# 3phasecntrl-rev2-1.net
KiCad netlist of a schematic drawn in EAGLE
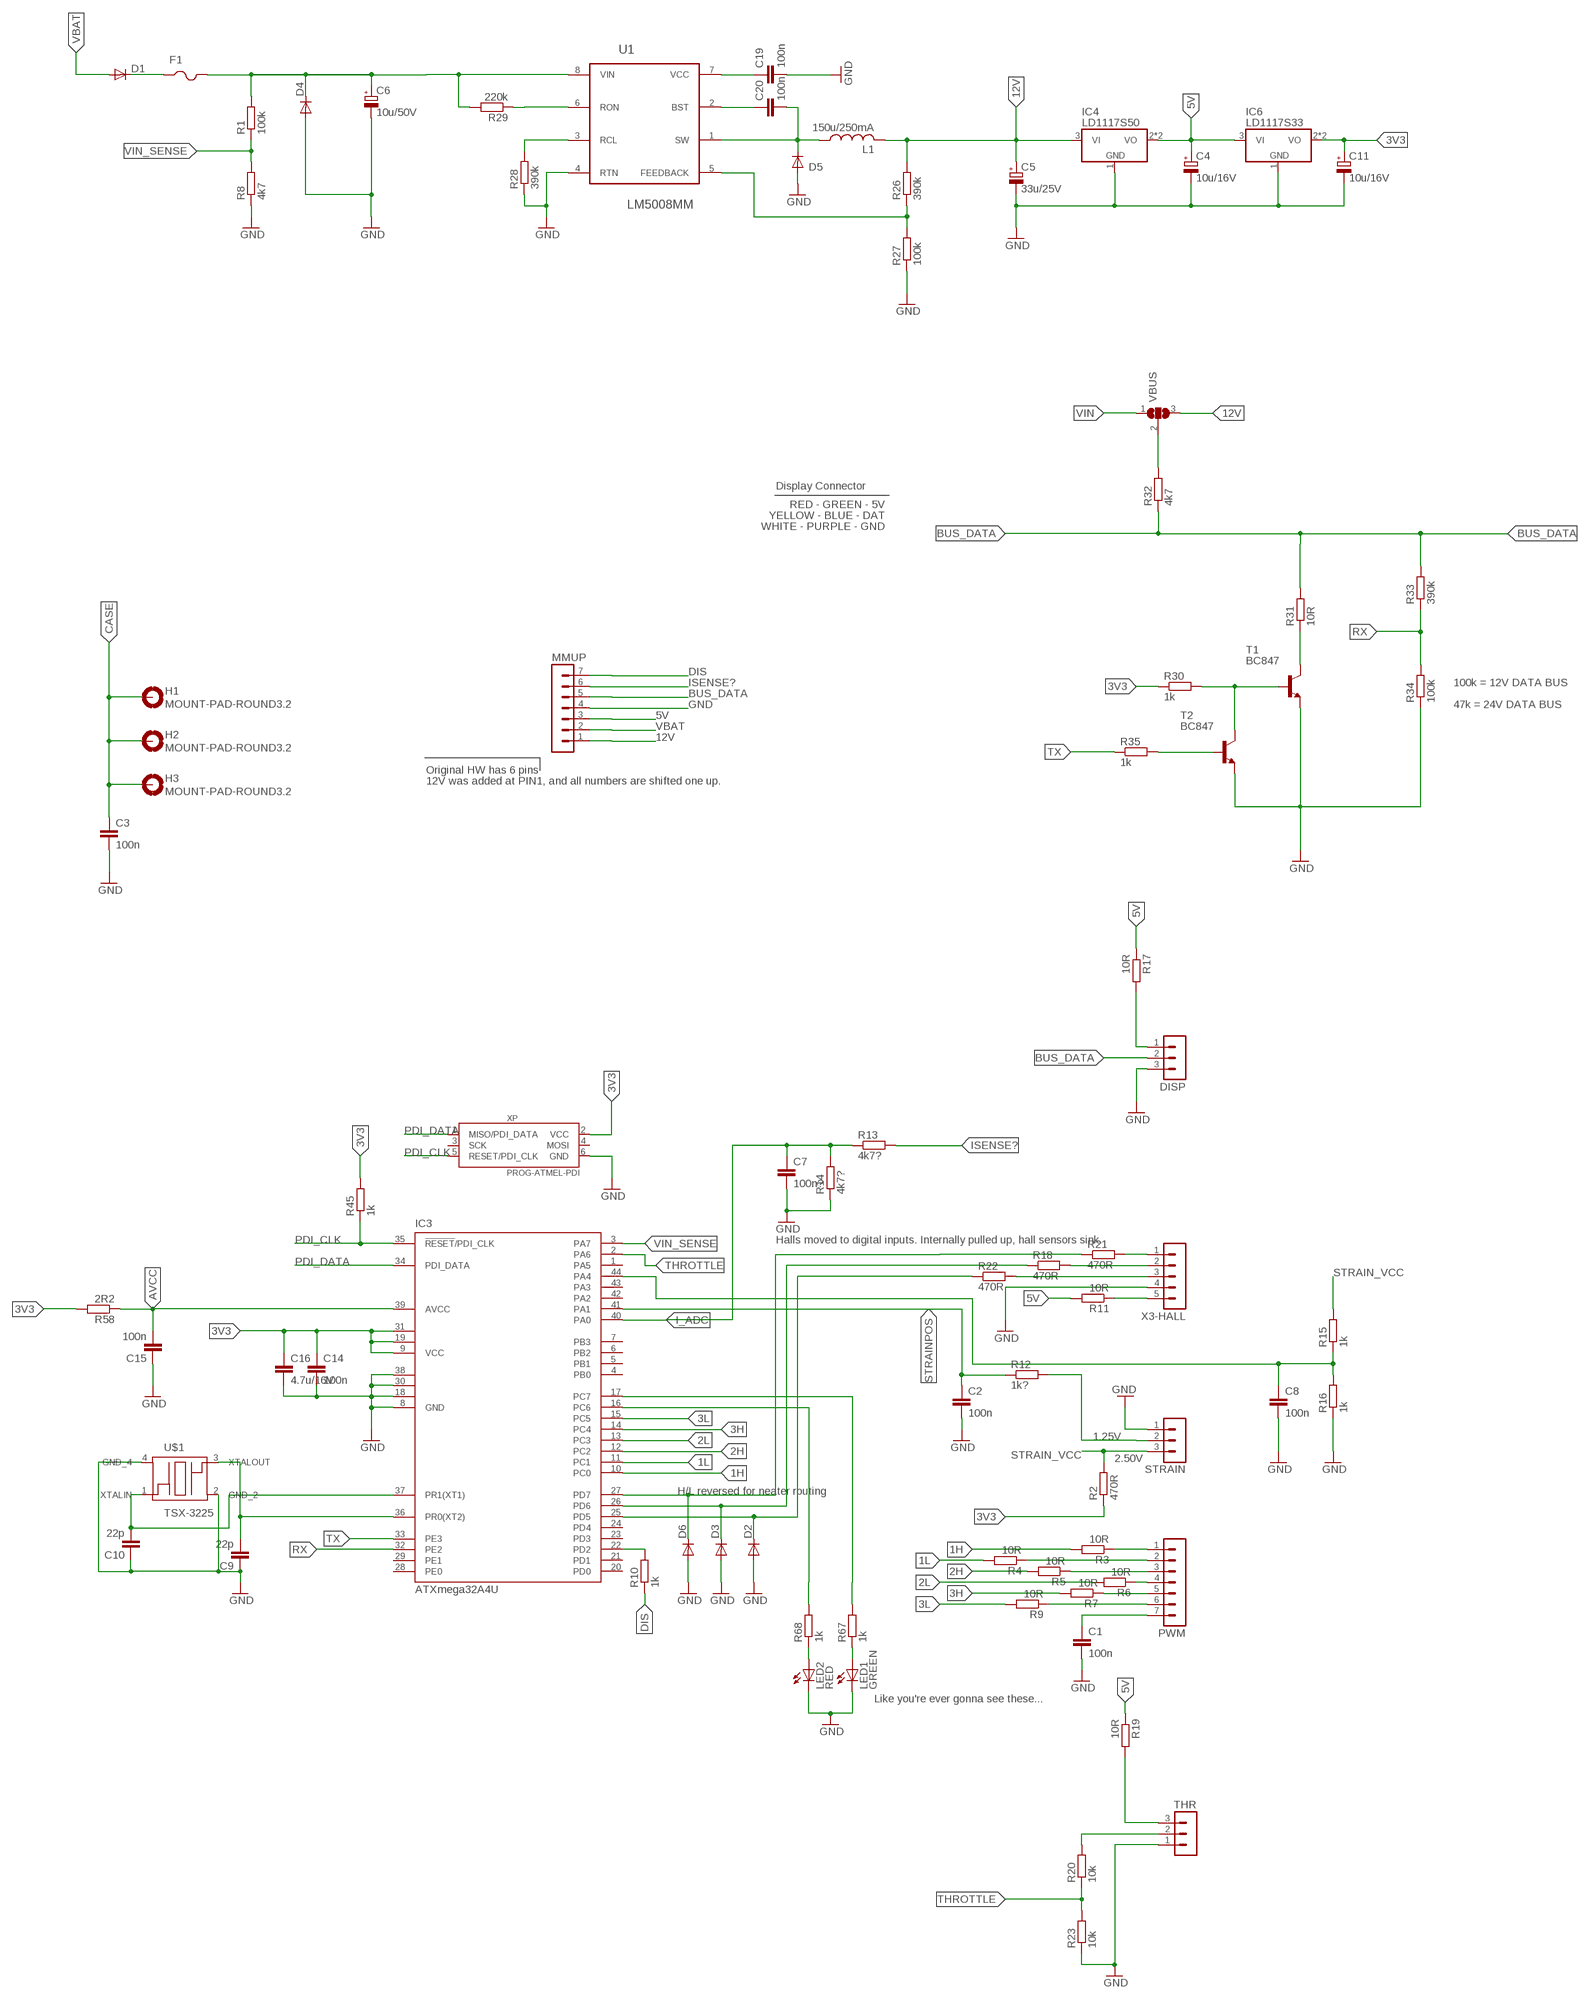
[diagram p0: schematic, sheet 1]

(export (version "E")
  (design (tool "Eeschema 10.0.6"))
  (components
    (comp (ref "C1")
      (value "100n")
      (footprint "eagle-import:C0805K")
      (libsource (lib "eagle-import") (part "C-EUC0805K"))
    )
    (comp (ref "C2")
      (value "100n")
      (footprint "eagle-import:C0805K")
      (libsource (lib "eagle-import") (part "C-EUC0805K"))
    )
    (comp (ref "C3")
      (value "100n")
      (footprint "eagle-import:C0805K")
      (libsource (lib "eagle-import") (part "C-EUC0805K"))
    )
    (comp (ref "C4")
      (value "10u/16V")
      (footprint "eagle-import:153CLV-0405")
      (libsource (lib "eagle-import") (part "CPOL-EU153CLV-0405"))
    )
    (comp (ref "C5")
      (value "33u/25V")
      (footprint "eagle-import:153CLV-0605")
      (libsource (lib "eagle-import") (part "CPOL-EU153CLV-0605"))
    )
    (comp (ref "C6")
      (value "10u/50V")
      (footprint "eagle-import:153CLV-0605")
      (libsource (lib "eagle-import") (part "CPOL-EU153CLV-0605"))
    )
    (comp (ref "C7")
      (value "100n?")
      (footprint "eagle-import:C0805K")
      (libsource (lib "eagle-import") (part "C-EUC0805K"))
    )
    (comp (ref "C8")
      (value "100n")
      (footprint "eagle-import:C0805K")
      (libsource (lib "eagle-import") (part "C-EUC0805K"))
    )
    (comp (ref "C9")
      (value "22p")
      (footprint "eagle-import:C0805K")
      (libsource (lib "eagle-import") (part "C-EUC0805K"))
    )
    (comp (ref "C10")
      (value "22p")
      (footprint "eagle-import:C0805K")
      (libsource (lib "eagle-import") (part "C-EUC0805K"))
    )
    (comp (ref "C11")
      (value "10u/16V")
      (footprint "eagle-import:153CLV-0405")
      (libsource (lib "eagle-import") (part "CPOL-EU153CLV-0405"))
    )
    (comp (ref "C14")
      (value "100n")
      (footprint "eagle-import:C0805K")
      (libsource (lib "eagle-import") (part "C-EUC0805K"))
    )
    (comp (ref "C15")
      (value "100n")
      (footprint "eagle-import:C0805K")
      (libsource (lib "eagle-import") (part "C-EUC0805K"))
    )
    (comp (ref "C16")
      (value "4.7u/16V")
      (footprint "eagle-import:C0805K")
      (libsource (lib "eagle-import") (part "C-EUC0805K"))
    )
    (comp (ref "C19")
      (value "100n")
      (footprint "eagle-import:C0805K")
      (libsource (lib "eagle-import") (part "C-EUC0805K"))
    )
    (comp (ref "C20")
      (value "100n")
      (footprint "eagle-import:C0805K")
      (libsource (lib "eagle-import") (part "C-EUC0805K"))
    )
    (comp (ref "D1")
      (value "BAT46WH")
      (footprint "eagle-import:SMB")
      (libsource (lib "eagle-import") (part "DIODE-SMB"))
    )
    (comp (ref "D2")
      (value "PTVS3V3S1UTR")
      (footprint "eagle-import:SOD123")
      (libsource (lib "eagle-import") (part "DIODE-SOD123"))
    )
    (comp (ref "D3")
      (value "PTVS3V3S1UTR")
      (footprint "eagle-import:SOD123")
      (libsource (lib "eagle-import") (part "DIODE-SOD123"))
    )
    (comp (ref "D4")
      (value "SM6T39A")
      (footprint "eagle-import:SMB")
      (libsource (lib "eagle-import") (part "DIODE-SMB"))
    )
    (comp (ref "D5")
      (value "BAT46WH")
      (footprint "eagle-import:SOD323-W")
      (libsource (lib "eagle-import") (part "DIODE-SOD323-W"))
    )
    (comp (ref "D6")
      (value "PTVS3V3S1UTR")
      (footprint "eagle-import:SOD123")
      (libsource (lib "eagle-import") (part "DIODE-SOD123"))
    )
    (comp (ref "DISP")
      (value "MA03-1")
      (footprint "eagle-import:MA03-1")
      (fields (field (name "OC_FARNELL") "unknown") (field (name "OC_NEWARK") "unknown"))
      (libsource (lib "eagle-import") (part "MA03-1"))
    )
    (comp (ref "F1")
      (value "PTCFUSE-1812")
      (footprint "eagle-import:1812")
      (libsource (lib "eagle-import") (part "PTCFUSE-1812"))
    )
    (comp (ref "H1")
      (value "MOUNT-PAD-ROUND3.2")
      (footprint "eagle-import:3,2-PAD")
      (libsource (lib "eagle-import") (part "MOUNT-PAD-ROUND3.2"))
    )
    (comp (ref "H2")
      (value "MOUNT-PAD-ROUND3.2")
      (footprint "eagle-import:3,2-PAD")
      (libsource (lib "eagle-import") (part "MOUNT-PAD-ROUND3.2"))
    )
    (comp (ref "H3")
      (value "MOUNT-PAD-ROUND3.2")
      (footprint "eagle-import:3,2-PAD")
      (libsource (lib "eagle-import") (part "MOUNT-PAD-ROUND3.2"))
    )
    (comp (ref "IC3")
      (value "ATXmega32A4U")
      (footprint "eagle-import:TQFP44")
      (libsource (lib "eagle-import") (part "XMEGA16A4A"))
    )
    (comp (ref "IC4")
      (value "LD1117S50")
      (footprint "eagle-import:SOT223")
      (libsource (lib "eagle-import") (part "LM340?-STST"))
    )
    (comp (ref "IC6")
      (value "LD1117S33")
      (footprint "eagle-import:SOT223")
      (libsource (lib "eagle-import") (part "LM340?-STST"))
    )
    (comp (ref "L1")
      (value "150u/250mA")
      (footprint "eagle-import:POWER-CHOKE_WE-TPC")
      (libsource (lib "eagle-import") (part "L-USWE-TPC"))
    )
    (comp (ref "LED1")
      (value "GREEN")
      (footprint "eagle-import:CHIPLED_0805")
      (libsource (lib "eagle-import") (part "LEDCHIPLED_0805"))
    )
    (comp (ref "LED2")
      (value "RED")
      (footprint "eagle-import:CHIPLED_0805")
      (libsource (lib "eagle-import") (part "LEDCHIPLED_0805"))
    )
    (comp (ref "MMUP")
      (value "MA07-1")
      (footprint "eagle-import:MA07-1")
      (fields (field (name "OC_FARNELL") "unknown") (field (name "OC_NEWARK") "unknown"))
      (libsource (lib "eagle-import") (part "MA07-1"))
    )
    (comp (ref "PWM")
      (value "MA07-1")
      (footprint "eagle-import:MA07-1")
      (libsource (lib "eagle-import") (part "MA07-1"))
    )
    (comp (ref "R1")
      (value "100k")
      (footprint "eagle-import:M0805")
      (libsource (lib "eagle-import") (part "R-EU_M0805"))
    )
    (comp (ref "R2")
      (value "470R")
      (footprint "eagle-import:M0805")
      (libsource (lib "eagle-import") (part "R-EU_M0805"))
    )
    (comp (ref "R3")
      (value "10R")
      (footprint "eagle-import:M0805")
      (libsource (lib "eagle-import") (part "R-EU_M0805"))
    )
    (comp (ref "R4")
      (value "10R")
      (footprint "eagle-import:M0805")
      (libsource (lib "eagle-import") (part "R-EU_M0805"))
    )
    (comp (ref "R5")
      (value "10R")
      (footprint "eagle-import:M0805")
      (libsource (lib "eagle-import") (part "R-EU_M0805"))
    )
    (comp (ref "R6")
      (value "10R")
      (footprint "eagle-import:M0805")
      (libsource (lib "eagle-import") (part "R-EU_M0805"))
    )
    (comp (ref "R7")
      (value "10R")
      (footprint "eagle-import:M0805")
      (libsource (lib "eagle-import") (part "R-EU_M0805"))
    )
    (comp (ref "R8")
      (value "4k7")
      (footprint "eagle-import:M0805")
      (libsource (lib "eagle-import") (part "R-EU_M0805"))
    )
    (comp (ref "R9")
      (value "10R")
      (footprint "eagle-import:M0805")
      (libsource (lib "eagle-import") (part "R-EU_M0805"))
    )
    (comp (ref "R10")
      (value "1k")
      (footprint "eagle-import:M0805")
      (libsource (lib "eagle-import") (part "R-EU_M0805"))
    )
    (comp (ref "R11")
      (value "10R")
      (footprint "eagle-import:M0805")
      (libsource (lib "eagle-import") (part "R-EU_M0805"))
    )
    (comp (ref "R12")
      (value "1k?")
      (footprint "eagle-import:M0805")
      (libsource (lib "eagle-import") (part "R-EU_M0805"))
    )
    (comp (ref "R13")
      (value "4k7?")
      (footprint "eagle-import:M0805")
      (libsource (lib "eagle-import") (part "R-EU_M0805"))
    )
    (comp (ref "R14")
      (value "4k7?")
      (footprint "eagle-import:M0805")
      (libsource (lib "eagle-import") (part "R-EU_M0805"))
    )
    (comp (ref "R15")
      (value "1k")
      (footprint "eagle-import:M0805")
      (libsource (lib "eagle-import") (part "R-EU_M0805"))
    )
    (comp (ref "R16")
      (value "1k")
      (footprint "eagle-import:M0805")
      (libsource (lib "eagle-import") (part "R-EU_M0805"))
    )
    (comp (ref "R17")
      (value "10R")
      (footprint "eagle-import:M0805")
      (libsource (lib "eagle-import") (part "R-EU_M0805"))
    )
    (comp (ref "R18")
      (value "470R")
      (footprint "eagle-import:M0805")
      (libsource (lib "eagle-import") (part "R-EU_M0805"))
    )
    (comp (ref "R19")
      (value "10R")
      (footprint "eagle-import:M0805")
      (libsource (lib "eagle-import") (part "R-EU_M0805"))
    )
    (comp (ref "R20")
      (value "10k")
      (footprint "eagle-import:M0805")
      (libsource (lib "eagle-import") (part "R-EU_M0805"))
    )
    (comp (ref "R21")
      (value "470R")
      (footprint "eagle-import:M0805")
      (libsource (lib "eagle-import") (part "R-EU_M0805"))
    )
    (comp (ref "R22")
      (value "470R")
      (footprint "eagle-import:M0805")
      (libsource (lib "eagle-import") (part "R-EU_M0805"))
    )
    (comp (ref "R23")
      (value "10k")
      (footprint "eagle-import:M0805")
      (libsource (lib "eagle-import") (part "R-EU_M0805"))
    )
    (comp (ref "R26")
      (value "390k")
      (footprint "eagle-import:M0805")
      (libsource (lib "eagle-import") (part "R-EU_M0805"))
    )
    (comp (ref "R27")
      (value "100k")
      (footprint "eagle-import:M0805")
      (libsource (lib "eagle-import") (part "R-EU_M0805"))
    )
    (comp (ref "R28")
      (value "390k")
      (footprint "eagle-import:M0805")
      (libsource (lib "eagle-import") (part "R-EU_M0805"))
    )
    (comp (ref "R29")
      (value "220k")
      (footprint "eagle-import:M0805")
      (libsource (lib "eagle-import") (part "R-EU_M0805"))
    )
    (comp (ref "R30")
      (value "1k")
      (footprint "eagle-import:M0805")
      (libsource (lib "eagle-import") (part "R-EU_M0805"))
    )
    (comp (ref "R31")
      (value "10R")
      (footprint "eagle-import:M0805")
      (libsource (lib "eagle-import") (part "R-EU_M0805"))
    )
    (comp (ref "R32")
      (value "4k7")
      (footprint "eagle-import:M0805")
      (libsource (lib "eagle-import") (part "R-EU_M0805"))
    )
    (comp (ref "R33")
      (value "390k")
      (footprint "eagle-import:M0805")
      (libsource (lib "eagle-import") (part "R-EU_M0805"))
    )
    (comp (ref "R34")
      (value "100k")
      (footprint "eagle-import:M0805")
      (libsource (lib "eagle-import") (part "R-EU_M0805"))
    )
    (comp (ref "R35")
      (value "1k")
      (footprint "eagle-import:M0805")
      (libsource (lib "eagle-import") (part "R-EU_M0805"))
    )
    (comp (ref "R45")
      (value "1k")
      (footprint "eagle-import:R0805")
      (libsource (lib "eagle-import") (part "R-EU_R0805"))
    )
    (comp (ref "R58")
      (value "2R2")
      (footprint "eagle-import:R0805")
      (libsource (lib "eagle-import") (part "R-EU_R0805"))
    )
    (comp (ref "R67")
      (value "1k")
      (footprint "eagle-import:M0805")
      (libsource (lib "eagle-import") (part "R-EU_M0805"))
    )
    (comp (ref "R68")
      (value "1k")
      (footprint "eagle-import:M0805")
      (libsource (lib "eagle-import") (part "R-EU_M0805"))
    )
    (comp (ref "STRAIN")
      (value "MA03-1")
      (footprint "eagle-import:MA03-1")
      (libsource (lib "eagle-import") (part "MA03-1"))
    )
    (comp (ref "T1")
      (value "BC847")
      (footprint "eagle-import:SOT23")
      (libsource (lib "eagle-import") (part "BC847"))
    )
    (comp (ref "T2")
      (value "BC847")
      (footprint "eagle-import:SOT23")
      (libsource (lib "eagle-import") (part "BC847"))
    )
    (comp (ref "THR")
      (value "MA03-1")
      (footprint "eagle-import:MA03-1")
      (libsource (lib "eagle-import") (part "MA03-1"))
    )
    (comp (ref "U$1")
      (value "TSX-3225")
      (footprint "eagle-import:TSX-3225")
      (libsource (lib "eagle-import") (part "TSX-3225"))
    )
    (comp (ref "U1")
      (value "LM5008MM")
      (footprint "eagle-import:SOP65P490X109-8N")
      (libsource (lib "eagle-import") (part "LM5008MM"))
    )
    (comp (ref "VBUS")
      (value "SJ2W")
      (footprint "eagle-import:SJ_2")
      (libsource (lib "eagle-import") (part "SJ2W"))
    )
    (comp (ref "X3-HALL")
      (value "MA05-1")
      (footprint "eagle-import:MA05-1")
      (libsource (lib "eagle-import") (part "MA05-1"))
    )
    (comp (ref "XP")
      (value "PROG-ATMEL-PDI")
      (footprint "eagle-import:6-LSTB2")
      (libsource (lib "eagle-import") (part "PROG-ATMEL-PDI"))
    )
  )
  (nets
    (net (code "1") (name "/PDI_CLK") (class "Default")
      (node (ref "IC3") (pin "35") (pinfunction "~{RESET}/PDI_CLK_35") (pintype "bidirectional"))
      (node (ref "R45") (pin "1") (pinfunction "1_1") (pintype "passive"))
      (node (ref "XP") (pin "5") (pinfunction "RESET/PDI_CLK_5") (pintype "bidirectional"))
    )
    (net (code "2") (name "/PDI_DATA") (class "Default")
      (node (ref "IC3") (pin "34") (pinfunction "PDI_DATA_34") (pintype "bidirectional"))
      (node (ref "XP") (pin "1") (pinfunction "MISO/PDI_DATA_1") (pintype "bidirectional"))
    )
    (net (code "3") (name "/STRAIN_VCC") (class "Default")
      (node (ref "R15") (pin "2") (pinfunction "2_2") (pintype "passive"))
      (node (ref "R2") (pin "2") (pinfunction "2_2") (pintype "passive"))
      (node (ref "STRAIN") (pin "3") (pinfunction "3_3") (pintype "passive"))
    )
    (net (code "4") (name "1H") (class "Default")
      (node (ref "IC3") (pin "10") (pinfunction "PC0_10") (pintype "bidirectional"))
      (node (ref "R3") (pin "2") (pinfunction "2_2") (pintype "passive"))
    )
    (net (code "5") (name "1L") (class "Default")
      (node (ref "IC3") (pin "11") (pinfunction "PC1_11") (pintype "bidirectional"))
      (node (ref "R4") (pin "2") (pinfunction "2_2") (pintype "passive"))
    )
    (net (code "6") (name "2H") (class "Default")
      (node (ref "IC3") (pin "12") (pinfunction "PC2_12") (pintype "bidirectional"))
      (node (ref "R5") (pin "2") (pinfunction "2_2") (pintype "passive"))
    )
    (net (code "7") (name "2L") (class "Default")
      (node (ref "IC3") (pin "13") (pinfunction "PC3_13") (pintype "bidirectional"))
      (node (ref "R6") (pin "2") (pinfunction "2_2") (pintype "passive"))
    )
    (net (code "8") (name "3H") (class "Default")
      (node (ref "IC3") (pin "14") (pinfunction "PC4_14") (pintype "bidirectional"))
      (node (ref "R7") (pin "2") (pinfunction "2_2") (pintype "passive"))
    )
    (net (code "9") (name "3L") (class "Default")
      (node (ref "IC3") (pin "15") (pinfunction "PC5_15") (pintype "bidirectional"))
      (node (ref "R9") (pin "2") (pinfunction "2_2") (pintype "passive"))
    )
    (net (code "10") (name "3V3") (class "Default")
      (node (ref "C11") (pin "+") (pinfunction "+_+") (pintype "passive"))
      (node (ref "C14") (pin "1") (pinfunction "1_1") (pintype "passive"))
      (node (ref "C16") (pin "1") (pinfunction "1_1") (pintype "passive"))
      (node (ref "IC3") (pin "19") (pinfunction "VCC1_19") (pintype "power_in"))
      (node (ref "IC3") (pin "31") (pinfunction "VCC2_31") (pintype "power_in"))
      (node (ref "IC3") (pin "9") (pinfunction "VCC_9") (pintype "power_in"))
      (node (ref "IC6") (pin "2") (pinfunction "VO_2") (pintype "passive"))
      (node (ref "IC6") (pin "4") (pinfunction "VO_4") (pintype "passive"))
      (node (ref "R2") (pin "1") (pinfunction "1_1") (pintype "passive"))
      (node (ref "R30") (pin "1") (pinfunction "1_1") (pintype "passive"))
      (node (ref "R45") (pin "2") (pinfunction "2_2") (pintype "passive"))
      (node (ref "R58") (pin "2") (pinfunction "2_2") (pintype "passive"))
      (node (ref "XP") (pin "2") (pinfunction "VCC_2") (pintype "bidirectional"))
    )
    (net (code "11") (name "5V") (class "Default")
      (node (ref "C4") (pin "+") (pinfunction "+_+") (pintype "passive"))
      (node (ref "IC4") (pin "2") (pinfunction "VO_2") (pintype "passive"))
      (node (ref "IC4") (pin "4") (pinfunction "VO_4") (pintype "passive"))
      (node (ref "IC6") (pin "3") (pinfunction "VI_3") (pintype "input"))
      (node (ref "MMUP") (pin "3") (pinfunction "3_3") (pintype "passive"))
      (node (ref "R11") (pin "2") (pinfunction "2_2") (pintype "passive"))
      (node (ref "R17") (pin "1") (pinfunction "1_1") (pintype "passive"))
      (node (ref "R19") (pin "1") (pinfunction "1_1") (pintype "passive"))
    )
    (net (code "12") (name "12V") (class "Default")
      (node (ref "C5") (pin "+") (pinfunction "+_+") (pintype "passive"))
      (node (ref "IC4") (pin "3") (pinfunction "VI_3") (pintype "input"))
      (node (ref "L1") (pin "2") (pinfunction "2_2") (pintype "passive"))
      (node (ref "MMUP") (pin "1") (pinfunction "1_1") (pintype "passive"))
      (node (ref "R26") (pin "2") (pinfunction "2_2") (pintype "passive"))
      (node (ref "VBUS") (pin "3") (pinfunction "3_3") (pintype "passive"))
    )
    (net (code "13") (name "AVCC") (class "Default")
      (node (ref "C15") (pin "2") (pinfunction "2_2") (pintype "passive"))
      (node (ref "IC3") (pin "39") (pinfunction "AVCC_39") (pintype "power_in"))
      (node (ref "R58") (pin "1") (pinfunction "1_1") (pintype "passive"))
    )
    (net (code "14") (name "BUS_DATA") (class "Default")
      (node (ref "DISP") (pin "2") (pinfunction "2_2") (pintype "passive"))
      (node (ref "MMUP") (pin "5") (pinfunction "5_5") (pintype "passive"))
      (node (ref "R31") (pin "2") (pinfunction "2_2") (pintype "passive"))
      (node (ref "R32") (pin "1") (pinfunction "1_1") (pintype "passive"))
      (node (ref "R33") (pin "2") (pinfunction "2_2") (pintype "passive"))
    )
    (net (code "15") (name "CASE") (class "Default")
      (node (ref "C3") (pin "1") (pinfunction "1_1") (pintype "passive"))
      (node (ref "H1") (pin "B3,2") (pinfunction "MOUNT_B3,2") (pintype "passive"))
      (node (ref "H2") (pin "B3,2") (pinfunction "MOUNT_B3,2") (pintype "passive"))
      (node (ref "H3") (pin "B3,2") (pinfunction "MOUNT_B3,2") (pintype "passive"))
    )
    (net (code "16") (name "DIS") (class "Default")
      (node (ref "MMUP") (pin "7") (pinfunction "7_7") (pintype "passive"))
      (node (ref "R10") (pin "1") (pinfunction "1_1") (pintype "passive"))
    )
    (net (code "17") (name "GND") (class "Default")
      (node (ref "C1") (pin "2") (pinfunction "2_2") (pintype "passive"))
      (node (ref "C10") (pin "1") (pinfunction "1_1") (pintype "passive"))
      (node (ref "C11") (pin "-") (pinfunction "-_-") (pintype "passive"))
      (node (ref "C14") (pin "2") (pinfunction "2_2") (pintype "passive"))
      (node (ref "C15") (pin "1") (pinfunction "1_1") (pintype "passive"))
      (node (ref "C16") (pin "2") (pinfunction "2_2") (pintype "passive"))
      (node (ref "C19") (pin "2") (pinfunction "2_2") (pintype "passive"))
      (node (ref "C2") (pin "2") (pinfunction "2_2") (pintype "passive"))
      (node (ref "C3") (pin "2") (pinfunction "2_2") (pintype "passive"))
      (node (ref "C4") (pin "-") (pinfunction "-_-") (pintype "passive"))
      (node (ref "C5") (pin "-") (pinfunction "-_-") (pintype "passive"))
      (node (ref "C6") (pin "-") (pinfunction "-_-") (pintype "passive"))
      (node (ref "C7") (pin "2") (pinfunction "2_2") (pintype "passive"))
      (node (ref "C8") (pin "2") (pinfunction "2_2") (pintype "passive"))
      (node (ref "C9") (pin "1") (pinfunction "1_1") (pintype "passive"))
      (node (ref "D2") (pin "A") (pinfunction "A_A") (pintype "passive"))
      (node (ref "D3") (pin "A") (pinfunction "A_A") (pintype "passive"))
      (node (ref "D4") (pin "A") (pinfunction "A_A") (pintype "passive"))
      (node (ref "D5") (pin "A") (pinfunction "A_A") (pintype "passive"))
      (node (ref "D6") (pin "A") (pinfunction "A_A") (pintype "passive"))
      (node (ref "DISP") (pin "3") (pinfunction "3_3") (pintype "passive"))
      (node (ref "IC3") (pin "18") (pinfunction "GND1_18") (pintype "power_in"))
      (node (ref "IC3") (pin "30") (pinfunction "GND2_30") (pintype "power_in"))
      (node (ref "IC3") (pin "38") (pinfunction "GND3_38") (pintype "power_in"))
      (node (ref "IC3") (pin "8") (pinfunction "GND_8") (pintype "power_in"))
      (node (ref "IC4") (pin "1") (pinfunction "GND_1") (pintype "passive"))
      (node (ref "IC6") (pin "1") (pinfunction "GND_1") (pintype "passive"))
      (node (ref "LED1") (pin "C") (pinfunction "C_C") (pintype "passive"))
      (node (ref "LED2") (pin "C") (pinfunction "C_C") (pintype "passive"))
      (node (ref "MMUP") (pin "4") (pinfunction "4_4") (pintype "passive"))
      (node (ref "R14") (pin "1") (pinfunction "1_1") (pintype "passive"))
      (node (ref "R16") (pin "1") (pinfunction "1_1") (pintype "passive"))
      (node (ref "R23") (pin "1") (pinfunction "1_1") (pintype "passive"))
      (node (ref "R27") (pin "1") (pinfunction "1_1") (pintype "passive"))
      (node (ref "R28") (pin "1") (pinfunction "1_1") (pintype "passive"))
      (node (ref "R34") (pin "1") (pinfunction "1_1") (pintype "passive"))
      (node (ref "R8") (pin "1") (pinfunction "1_1") (pintype "passive"))
      (node (ref "STRAIN") (pin "1") (pinfunction "1_1") (pintype "passive"))
      (node (ref "T1") (pin "2") (pinfunction "E_2") (pintype "passive"))
      (node (ref "T2") (pin "2") (pinfunction "E_2") (pintype "passive"))
      (node (ref "THR") (pin "1") (pinfunction "1_1") (pintype "passive"))
      (node (ref "U$1") (pin "2") (pinfunction "GND_2_2") (pintype "bidirectional"))
      (node (ref "U$1") (pin "4") (pinfunction "GND_4_4") (pintype "bidirectional"))
      (node (ref "U1") (pin "4") (pinfunction "RTN_4") (pintype "passive"))
      (node (ref "X3-HALL") (pin "4") (pinfunction "4_4") (pintype "passive"))
      (node (ref "XP") (pin "6") (pinfunction "GND_6") (pintype "bidirectional"))
    )
    (net (code "18") (name "ISENSE?") (class "Default")
      (node (ref "MMUP") (pin "6") (pinfunction "6_6") (pintype "passive"))
      (node (ref "R13") (pin "2") (pinfunction "2_2") (pintype "passive"))
    )
    (net (code "19") (name "I_ADC") (class "Default")
      (node (ref "C7") (pin "1") (pinfunction "1_1") (pintype "passive"))
      (node (ref "IC3") (pin "40") (pinfunction "PA0_40") (pintype "bidirectional"))
      (node (ref "R13") (pin "1") (pinfunction "1_1") (pintype "passive"))
      (node (ref "R14") (pin "2") (pinfunction "2_2") (pintype "passive"))
    )
    (net (code "20") (name "Net-(C1-Pad1)") (class "Default")
      (node (ref "C1") (pin "1") (pinfunction "1_1") (pintype "passive"))
      (node (ref "PWM") (pin "7") (pinfunction "7_7") (pintype "passive"))
    )
    (net (code "21") (name "Net-(D1-PadC)") (class "Default")
      (node (ref "D1") (pin "C") (pinfunction "C_C") (pintype "passive"))
      (node (ref "F1") (pin "1") (pinfunction "1_1") (pintype "passive"))
    )
    (net (code "22") (name "Net-(DISP-Pad1)") (class "Default")
      (node (ref "DISP") (pin "1") (pinfunction "1_1") (pintype "passive"))
      (node (ref "R17") (pin "2") (pinfunction "2_2") (pintype "passive"))
    )
    (net (code "23") (name "Net-(IC3-PA4)") (class "Default")
      (node (ref "C8") (pin "1") (pinfunction "1_1") (pintype "passive"))
      (node (ref "IC3") (pin "44") (pinfunction "PA4_44") (pintype "bidirectional"))
      (node (ref "R15") (pin "1") (pinfunction "1_1") (pintype "passive"))
      (node (ref "R16") (pin "2") (pinfunction "2_2") (pintype "passive"))
    )
    (net (code "24") (name "Net-(IC3-PC6)") (class "Default")
      (node (ref "IC3") (pin "16") (pinfunction "PC6_16") (pintype "bidirectional"))
      (node (ref "R68") (pin "2") (pinfunction "2_2") (pintype "passive"))
    )
    (net (code "25") (name "Net-(IC3-PC7)") (class "Default")
      (node (ref "IC3") (pin "17") (pinfunction "PC7_17") (pintype "bidirectional"))
      (node (ref "R67") (pin "2") (pinfunction "2_2") (pintype "passive"))
    )
    (net (code "26") (name "Net-(IC3-PD2)") (class "Default")
      (node (ref "IC3") (pin "22") (pinfunction "PD2_22") (pintype "bidirectional"))
      (node (ref "R10") (pin "2") (pinfunction "2_2") (pintype "passive"))
    )
    (net (code "27") (name "Net-(IC3-PD5)") (class "Default")
      (node (ref "D2") (pin "C") (pinfunction "C_C") (pintype "passive"))
      (node (ref "IC3") (pin "25") (pinfunction "PD5_25") (pintype "bidirectional"))
      (node (ref "R22") (pin "1") (pinfunction "1_1") (pintype "passive"))
    )
    (net (code "28") (name "Net-(IC3-PD6)") (class "Default")
      (node (ref "D3") (pin "C") (pinfunction "C_C") (pintype "passive"))
      (node (ref "IC3") (pin "26") (pinfunction "PD6_26") (pintype "bidirectional"))
      (node (ref "R18") (pin "1") (pinfunction "1_1") (pintype "passive"))
    )
    (net (code "29") (name "Net-(IC3-PD7)") (class "Default")
      (node (ref "D6") (pin "C") (pinfunction "C_C") (pintype "passive"))
      (node (ref "IC3") (pin "27") (pinfunction "PD7_27") (pintype "bidirectional"))
      (node (ref "R21") (pin "1") (pinfunction "1_1") (pintype "passive"))
    )
    (net (code "30") (name "Net-(IC3-PR0(XT2))") (class "Default")
      (node (ref "C9") (pin "2") (pinfunction "2_2") (pintype "passive"))
      (node (ref "IC3") (pin "36") (pinfunction "PR0(XT2)_36") (pintype "bidirectional"))
      (node (ref "U$1") (pin "3") (pinfunction "XTALOUT_3") (pintype "bidirectional"))
    )
    (net (code "31") (name "Net-(IC3-PR1(XT1))") (class "Default")
      (node (ref "C10") (pin "2") (pinfunction "2_2") (pintype "passive"))
      (node (ref "IC3") (pin "37") (pinfunction "PR1(XT1)_37") (pintype "bidirectional"))
      (node (ref "U$1") (pin "1") (pinfunction "XTALIN_1") (pintype "bidirectional"))
    )
    (net (code "32") (name "Net-(LED1-PadA)") (class "Default")
      (node (ref "LED1") (pin "A") (pinfunction "A_A") (pintype "passive"))
      (node (ref "R67") (pin "1") (pinfunction "1_1") (pintype "passive"))
    )
    (net (code "33") (name "Net-(LED2-PadA)") (class "Default")
      (node (ref "LED2") (pin "A") (pinfunction "A_A") (pintype "passive"))
      (node (ref "R68") (pin "1") (pinfunction "1_1") (pintype "passive"))
    )
    (net (code "34") (name "Net-(PWM-Pad1)") (class "Default")
      (node (ref "PWM") (pin "1") (pinfunction "1_1") (pintype "passive"))
      (node (ref "R3") (pin "1") (pinfunction "1_1") (pintype "passive"))
    )
    (net (code "35") (name "Net-(PWM-Pad2)") (class "Default")
      (node (ref "PWM") (pin "2") (pinfunction "2_2") (pintype "passive"))
      (node (ref "R4") (pin "1") (pinfunction "1_1") (pintype "passive"))
    )
    (net (code "36") (name "Net-(PWM-Pad3)") (class "Default")
      (node (ref "PWM") (pin "3") (pinfunction "3_3") (pintype "passive"))
      (node (ref "R5") (pin "1") (pinfunction "1_1") (pintype "passive"))
    )
    (net (code "37") (name "Net-(PWM-Pad4)") (class "Default")
      (node (ref "PWM") (pin "4") (pinfunction "4_4") (pintype "passive"))
      (node (ref "R6") (pin "1") (pinfunction "1_1") (pintype "passive"))
    )
    (net (code "38") (name "Net-(PWM-Pad5)") (class "Default")
      (node (ref "PWM") (pin "5") (pinfunction "5_5") (pintype "passive"))
      (node (ref "R7") (pin "1") (pinfunction "1_1") (pintype "passive"))
    )
    (net (code "39") (name "Net-(PWM-Pad6)") (class "Default")
      (node (ref "PWM") (pin "6") (pinfunction "6_6") (pintype "passive"))
      (node (ref "R9") (pin "1") (pinfunction "1_1") (pintype "passive"))
    )
    (net (code "40") (name "Net-(R11-Pad1)") (class "Default")
      (node (ref "R11") (pin "1") (pinfunction "1_1") (pintype "passive"))
      (node (ref "X3-HALL") (pin "5") (pinfunction "5_5") (pintype "passive"))
    )
    (net (code "41") (name "Net-(R12-Pad2)") (class "Default")
      (node (ref "R12") (pin "2") (pinfunction "2_2") (pintype "passive"))
      (node (ref "STRAIN") (pin "2") (pinfunction "2_2") (pintype "passive"))
    )
    (net (code "42") (name "Net-(R18-Pad2)") (class "Default")
      (node (ref "R18") (pin "2") (pinfunction "2_2") (pintype "passive"))
      (node (ref "X3-HALL") (pin "2") (pinfunction "2_2") (pintype "passive"))
    )
    (net (code "43") (name "Net-(R19-Pad2)") (class "Default")
      (node (ref "R19") (pin "2") (pinfunction "2_2") (pintype "passive"))
      (node (ref "THR") (pin "3") (pinfunction "3_3") (pintype "passive"))
    )
    (net (code "44") (name "Net-(R20-Pad2)") (class "Default")
      (node (ref "R20") (pin "2") (pinfunction "2_2") (pintype "passive"))
      (node (ref "THR") (pin "2") (pinfunction "2_2") (pintype "passive"))
    )
    (net (code "45") (name "Net-(R21-Pad2)") (class "Default")
      (node (ref "R21") (pin "2") (pinfunction "2_2") (pintype "passive"))
      (node (ref "X3-HALL") (pin "1") (pinfunction "1_1") (pintype "passive"))
    )
    (net (code "46") (name "Net-(R22-Pad2)") (class "Default")
      (node (ref "R22") (pin "2") (pinfunction "2_2") (pintype "passive"))
      (node (ref "X3-HALL") (pin "3") (pinfunction "3_3") (pintype "passive"))
    )
    (net (code "47") (name "Net-(R32-Pad2)") (class "Default")
      (node (ref "R32") (pin "2") (pinfunction "2_2") (pintype "passive"))
      (node (ref "VBUS") (pin "2") (pinfunction "2_2") (pintype "passive"))
    )
    (net (code "48") (name "Net-(T1-B)") (class "Default")
      (node (ref "R30") (pin "2") (pinfunction "2_2") (pintype "passive"))
      (node (ref "T1") (pin "1") (pinfunction "B_1") (pintype "passive"))
      (node (ref "T2") (pin "3") (pinfunction "C_3") (pintype "passive"))
    )
    (net (code "49") (name "Net-(T1-C)") (class "Default")
      (node (ref "R31") (pin "1") (pinfunction "1_1") (pintype "passive"))
      (node (ref "T1") (pin "3") (pinfunction "C_3") (pintype "passive"))
    )
    (net (code "50") (name "Net-(T2-B)") (class "Default")
      (node (ref "R35") (pin "2") (pinfunction "2_2") (pintype "passive"))
      (node (ref "T2") (pin "1") (pinfunction "B_1") (pintype "passive"))
    )
    (net (code "51") (name "Net-(U1-BST)") (class "Default")
      (node (ref "C20") (pin "1") (pinfunction "1_1") (pintype "passive"))
      (node (ref "U1") (pin "2") (pinfunction "BST_2") (pintype "passive"))
    )
    (net (code "52") (name "Net-(U1-FEEDBACK)") (class "Default")
      (node (ref "R26") (pin "1") (pinfunction "1_1") (pintype "passive"))
      (node (ref "R27") (pin "2") (pinfunction "2_2") (pintype "passive"))
      (node (ref "U1") (pin "5") (pinfunction "FEEDBACK_5") (pintype "input"))
    )
    (net (code "53") (name "Net-(U1-RCL)") (class "Default")
      (node (ref "R28") (pin "2") (pinfunction "2_2") (pintype "passive"))
      (node (ref "U1") (pin "3") (pinfunction "RCL_3") (pintype "passive"))
    )
    (net (code "54") (name "Net-(U1-RON)") (class "Default")
      (node (ref "R29") (pin "1") (pinfunction "1_1") (pintype "passive"))
      (node (ref "U1") (pin "6") (pinfunction "RON_6") (pintype "input"))
    )
    (net (code "55") (name "Net-(U1-SW)") (class "Default")
      (node (ref "C20") (pin "2") (pinfunction "2_2") (pintype "passive"))
      (node (ref "D5") (pin "C") (pinfunction "C_C") (pintype "passive"))
      (node (ref "L1") (pin "1") (pinfunction "1_1") (pintype "passive"))
      (node (ref "U1") (pin "1") (pinfunction "SW_1") (pintype "output"))
    )
    (net (code "56") (name "Net-(U1-VCC)") (class "Default")
      (node (ref "C19") (pin "1") (pinfunction "1_1") (pintype "passive"))
      (node (ref "U1") (pin "7") (pinfunction "VCC_7") (pintype "power_in"))
    )
    (net (code "57") (name "RX") (class "Default")
      (node (ref "IC3") (pin "32") (pinfunction "PE2_32") (pintype "bidirectional"))
      (node (ref "R33") (pin "1") (pinfunction "1_1") (pintype "passive"))
      (node (ref "R34") (pin "2") (pinfunction "2_2") (pintype "passive"))
    )
    (net (code "58") (name "STRAINPOS") (class "Default")
      (node (ref "C2") (pin "1") (pinfunction "1_1") (pintype "passive"))
      (node (ref "IC3") (pin "41") (pinfunction "PA1_41") (pintype "bidirectional"))
      (node (ref "R12") (pin "1") (pinfunction "1_1") (pintype "passive"))
    )
    (net (code "59") (name "THROTTLE") (class "Default")
      (node (ref "IC3") (pin "2") (pinfunction "PA6_2") (pintype "bidirectional"))
      (node (ref "R20") (pin "1") (pinfunction "1_1") (pintype "passive"))
      (node (ref "R23") (pin "2") (pinfunction "2_2") (pintype "passive"))
    )
    (net (code "60") (name "TX") (class "Default")
      (node (ref "IC3") (pin "33") (pinfunction "PE3_33") (pintype "bidirectional"))
      (node (ref "R35") (pin "1") (pinfunction "1_1") (pintype "passive"))
    )
    (net (code "61") (name "VBAT") (class "Default")
      (node (ref "D1") (pin "A") (pinfunction "A_A") (pintype "passive"))
      (node (ref "MMUP") (pin "2") (pinfunction "2_2") (pintype "passive"))
    )
    (net (code "62") (name "VIN") (class "Default")
      (node (ref "C6") (pin "+") (pinfunction "+_+") (pintype "passive"))
      (node (ref "D4") (pin "C") (pinfunction "C_C") (pintype "passive"))
      (node (ref "F1") (pin "2") (pinfunction "2_2") (pintype "passive"))
      (node (ref "R1") (pin "2") (pinfunction "2_2") (pintype "passive"))
      (node (ref "R29") (pin "2") (pinfunction "2_2") (pintype "passive"))
      (node (ref "U1") (pin "8") (pinfunction "VIN_8") (pintype "power_in"))
      (node (ref "VBUS") (pin "1") (pinfunction "1_1") (pintype "passive"))
    )
    (net (code "63") (name "VIN_SENSE") (class "Default")
      (node (ref "IC3") (pin "3") (pinfunction "PA7_3") (pintype "bidirectional"))
      (node (ref "R1") (pin "1") (pinfunction "1_1") (pintype "passive"))
      (node (ref "R8") (pin "2") (pinfunction "2_2") (pintype "passive"))
    )
    (net (code "64") (name "unconnected-(IC3-PA2-Pad42)") (class "Default")
      (node (ref "IC3") (pin "42") (pinfunction "PA2_42") (pintype "bidirectional"))
    )
    (net (code "65") (name "unconnected-(IC3-PA3-Pad43)") (class "Default")
      (node (ref "IC3") (pin "43") (pinfunction "PA3_43") (pintype "bidirectional"))
    )
    (net (code "66") (name "unconnected-(IC3-PA5-Pad1)") (class "Default")
      (node (ref "IC3") (pin "1") (pinfunction "PA5_1") (pintype "bidirectional"))
    )
    (net (code "67") (name "unconnected-(IC3-PB0-Pad4)") (class "Default")
      (node (ref "IC3") (pin "4") (pinfunction "PB0_4") (pintype "bidirectional"))
    )
    (net (code "68") (name "unconnected-(IC3-PB1-Pad5)") (class "Default")
      (node (ref "IC3") (pin "5") (pinfunction "PB1_5") (pintype "bidirectional"))
    )
    (net (code "69") (name "unconnected-(IC3-PB2-Pad6)") (class "Default")
      (node (ref "IC3") (pin "6") (pinfunction "PB2_6") (pintype "bidirectional"))
    )
    (net (code "70") (name "unconnected-(IC3-PB3-Pad7)") (class "Default")
      (node (ref "IC3") (pin "7") (pinfunction "PB3_7") (pintype "bidirectional"))
    )
    (net (code "71") (name "unconnected-(IC3-PD0-Pad20)") (class "Default")
      (node (ref "IC3") (pin "20") (pinfunction "PD0_20") (pintype "bidirectional"))
    )
    (net (code "72") (name "unconnected-(IC3-PD1-Pad21)") (class "Default")
      (node (ref "IC3") (pin "21") (pinfunction "PD1_21") (pintype "bidirectional"))
    )
    (net (code "73") (name "unconnected-(IC3-PD3-Pad23)") (class "Default")
      (node (ref "IC3") (pin "23") (pinfunction "PD3_23") (pintype "bidirectional"))
    )
    (net (code "74") (name "unconnected-(IC3-PD4-Pad24)") (class "Default")
      (node (ref "IC3") (pin "24") (pinfunction "PD4_24") (pintype "bidirectional"))
    )
    (net (code "75") (name "unconnected-(IC3-PE0-Pad28)") (class "Default")
      (node (ref "IC3") (pin "28") (pinfunction "PE0_28") (pintype "bidirectional"))
    )
    (net (code "76") (name "unconnected-(IC3-PE1-Pad29)") (class "Default")
      (node (ref "IC3") (pin "29") (pinfunction "PE1_29") (pintype "bidirectional"))
    )
    (net (code "77") (name "unconnected-(XP-MOSI-Pad4)") (class "Default")
      (node (ref "XP") (pin "4") (pinfunction "MOSI_4") (pintype "bidirectional"))
    )
    (net (code "78") (name "unconnected-(XP-SCK-Pad3)") (class "Default")
      (node (ref "XP") (pin "3") (pinfunction "SCK_3") (pintype "bidirectional"))
    )
  )
)
